# netSpeed.net
KiCad netlist of a schematic drawn in EAGLE
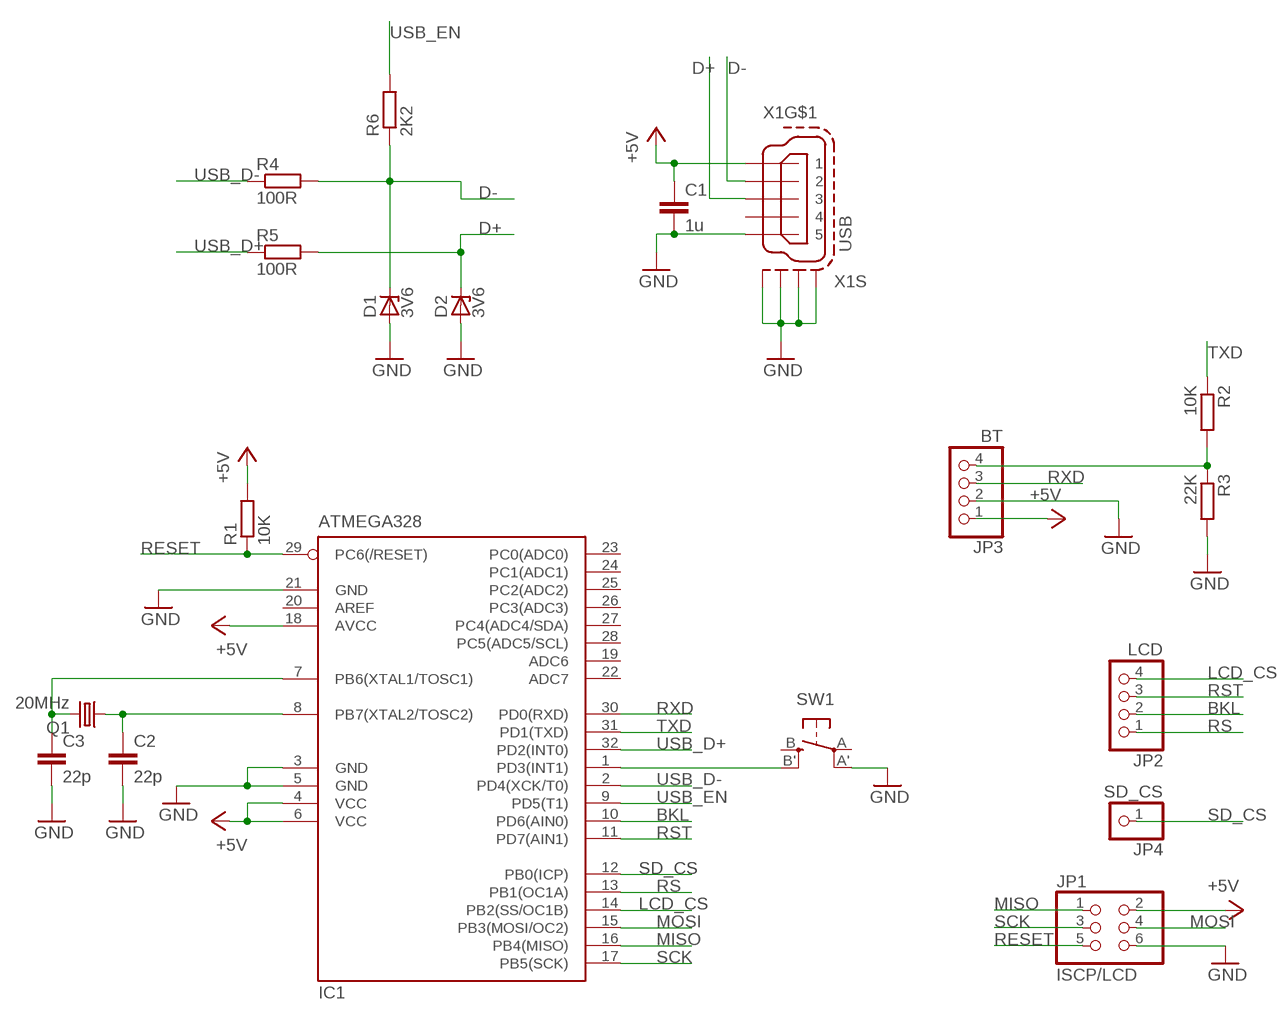
[diagram p0: schematic, sheet 1]

(export (version "E")
  (design (tool "Eeschema 10.0.6"))
  (components
    (comp (ref "C1")
      (value "1u")
      (footprint "eagle-import:C0805")
      (libsource (lib "eagle-import") (part "C-EUC0805"))
    )
    (comp (ref "C2")
      (value "22p")
      (footprint "eagle-import:C0805")
      (libsource (lib "eagle-import") (part "C-EUC0805"))
    )
    (comp (ref "C3")
      (value "22p")
      (footprint "eagle-import:C0805")
      (libsource (lib "eagle-import") (part "C-EUC0805"))
    )
    (comp (ref "D1")
      (value "3V6")
      (footprint "eagle-import:ZDIO-2.5")
      (libsource (lib "eagle-import") (part "ZENER-DIODEZD-2.5"))
    )
    (comp (ref "D2")
      (value "3V6")
      (footprint "eagle-import:ZDIO-2.5")
      (libsource (lib "eagle-import") (part "ZENER-DIODEZD-2.5"))
    )
    (comp (ref "IC1")
      (value "ATMEGA328")
      (footprint "eagle-import:TQFP32-08")
      (fields (field (name "MPN") "ATMEGA8-16AU"))
      (libsource (lib "eagle-import") (part "MEGA8-AI"))
    )
    (comp (ref "JP1")
      (value "ISCP/LCD")
      (footprint "eagle-import:2X03")
      (libsource (lib "eagle-import") (part "PINHD-2X3"))
    )
    (comp (ref "JP2")
      (value "LCD")
      (footprint "eagle-import:1X04")
      (libsource (lib "eagle-import") (part "PINHD-1X4"))
    )
    (comp (ref "JP3")
      (value "BT")
      (footprint "eagle-import:1X04")
      (libsource (lib "eagle-import") (part "PINHD-1X4"))
    )
    (comp (ref "JP4")
      (value "SD_CS")
      (footprint "eagle-import:1X01")
      (libsource (lib "eagle-import") (part "PINHD-1X1"))
    )
    (comp (ref "Q1")
      (value "20MHz")
      (footprint "eagle-import:HC49UP")
      (libsource (lib "eagle-import") (part "CRYSTALHC49UP"))
    )
    (comp (ref "R1")
      (value "10K")
      (footprint "eagle-import:M0805")
      (libsource (lib "eagle-import") (part "R-EU_M0805"))
    )
    (comp (ref "R2")
      (value "10K")
      (footprint "eagle-import:M0805")
      (libsource (lib "eagle-import") (part "R-EU_M0805"))
    )
    (comp (ref "R3")
      (value "22K")
      (footprint "eagle-import:M0805")
      (libsource (lib "eagle-import") (part "R-EU_M0805"))
    )
    (comp (ref "R4")
      (value "100R")
      (footprint "eagle-import:M0805")
      (libsource (lib "eagle-import") (part "R-EU_M0805"))
    )
    (comp (ref "R5")
      (value "100R")
      (footprint "eagle-import:M0805")
      (libsource (lib "eagle-import") (part "R-EU_M0805"))
    )
    (comp (ref "R6")
      (value "2K2")
      (footprint "eagle-import:M0805")
      (libsource (lib "eagle-import") (part "R-EU_M0805"))
    )
    (comp (ref "SW1")
      (value "SPST_TACT-EVQQ2")
      (footprint "eagle-import:EVQ-Q2")
      (libsource (lib "eagle-import") (part "SPST_TACT-EVQQ2"))
    )
    (comp (ref "X1")
      (value "USB")
      (footprint "eagle-import:32005-201")
      (libsource (lib "eagle-import") (part "MINI-USB-SCHIELD-32005-201"))
    )
  )
  (nets
    (net (code "1") (name "+5V") (class "Default")
      (node (ref "C1") (pin "1") (pinfunction "1_1") (pintype "passive"))
      (node (ref "IC1") (pin "18") (pinfunction "AVCC_18") (pintype "power_in"))
      (node (ref "IC1") (pin "4") (pinfunction "VCC_4") (pintype "power_in"))
      (node (ref "IC1") (pin "6") (pinfunction "VCC_6") (pintype "power_in"))
      (node (ref "JP1") (pin "2") (pinfunction "2_2") (pintype "passive"))
      (node (ref "JP3") (pin "1") (pinfunction "1_1") (pintype "passive"))
      (node (ref "R1") (pin "2") (pinfunction "2_2") (pintype "passive"))
      (node (ref "X1") (pin "1") (pinfunction "1_1") (pintype "passive"))
    )
    (net (code "2") (name "/BKL") (class "Default")
      (node (ref "IC1") (pin "10") (pinfunction "PD6(AIN0)_10") (pintype "bidirectional"))
      (node (ref "JP2") (pin "2") (pinfunction "2_2") (pintype "passive"))
    )
    (net (code "3") (name "/D+") (class "Default")
      (node (ref "D2") (pin "C") (pinfunction "C_C") (pintype "passive"))
      (node (ref "R5") (pin "2") (pinfunction "2_2") (pintype "passive"))
      (node (ref "X1") (pin "3") (pinfunction "3_3") (pintype "passive"))
    )
    (net (code "4") (name "/D-") (class "Default")
      (node (ref "D1") (pin "C") (pinfunction "C_C") (pintype "passive"))
      (node (ref "R4") (pin "2") (pinfunction "2_2") (pintype "passive"))
      (node (ref "R6") (pin "1") (pinfunction "1_1") (pintype "passive"))
      (node (ref "X1") (pin "2") (pinfunction "2_2") (pintype "passive"))
    )
    (net (code "5") (name "/LCD_CS") (class "Default")
      (node (ref "IC1") (pin "14") (pinfunction "PB2(SS/OC1B)_14") (pintype "bidirectional"))
      (node (ref "JP2") (pin "4") (pinfunction "4_4") (pintype "passive"))
    )
    (net (code "6") (name "/MISO") (class "Default")
      (node (ref "IC1") (pin "16") (pinfunction "PB4(MISO)_16") (pintype "bidirectional"))
      (node (ref "JP1") (pin "1") (pinfunction "1_1") (pintype "passive"))
    )
    (net (code "7") (name "/MOSI") (class "Default")
      (node (ref "IC1") (pin "15") (pinfunction "PB3(MOSI/OC2)_15") (pintype "bidirectional"))
      (node (ref "JP1") (pin "4") (pinfunction "4_4") (pintype "passive"))
    )
    (net (code "8") (name "/RESET") (class "Default")
      (node (ref "IC1") (pin "29") (pinfunction "PC6(/RESET)_29") (pintype "bidirectional"))
      (node (ref "JP1") (pin "5") (pinfunction "5_5") (pintype "passive"))
      (node (ref "R1") (pin "1") (pinfunction "1_1") (pintype "passive"))
    )
    (net (code "9") (name "/RS") (class "Default")
      (node (ref "IC1") (pin "13") (pinfunction "PB1(OC1A)_13") (pintype "bidirectional"))
      (node (ref "JP2") (pin "1") (pinfunction "1_1") (pintype "passive"))
    )
    (net (code "10") (name "/RST") (class "Default")
      (node (ref "IC1") (pin "11") (pinfunction "PD7(AIN1)_11") (pintype "bidirectional"))
      (node (ref "JP2") (pin "3") (pinfunction "3_3") (pintype "passive"))
    )
    (net (code "11") (name "/RXD") (class "Default")
      (node (ref "IC1") (pin "30") (pinfunction "PD0(RXD)_30") (pintype "bidirectional"))
      (node (ref "JP3") (pin "3") (pinfunction "3_3") (pintype "passive"))
    )
    (net (code "12") (name "/SCK") (class "Default")
      (node (ref "IC1") (pin "17") (pinfunction "PB5(SCK)_17") (pintype "bidirectional"))
      (node (ref "JP1") (pin "3") (pinfunction "3_3") (pintype "passive"))
    )
    (net (code "13") (name "/SD_CS") (class "Default")
      (node (ref "IC1") (pin "12") (pinfunction "PB0(ICP)_12") (pintype "bidirectional"))
      (node (ref "JP4") (pin "1") (pinfunction "1_1") (pintype "passive"))
    )
    (net (code "14") (name "/TXD") (class "Default")
      (node (ref "IC1") (pin "31") (pinfunction "PD1(TXD)_31") (pintype "bidirectional"))
      (node (ref "R2") (pin "1") (pinfunction "1_1") (pintype "passive"))
    )
    (net (code "15") (name "/USB_D+") (class "Default")
      (node (ref "IC1") (pin "32") (pinfunction "PD2(INT0)_32") (pintype "bidirectional"))
      (node (ref "R5") (pin "1") (pinfunction "1_1") (pintype "passive"))
    )
    (net (code "16") (name "/USB_D-") (class "Default")
      (node (ref "IC1") (pin "2") (pinfunction "PD4(XCK/T0)_2") (pintype "bidirectional"))
      (node (ref "R4") (pin "1") (pinfunction "1_1") (pintype "passive"))
    )
    (net (code "17") (name "/USB_EN") (class "Default")
      (node (ref "IC1") (pin "9") (pinfunction "PD5(T1)_9") (pintype "bidirectional"))
      (node (ref "R6") (pin "2") (pinfunction "2_2") (pintype "passive"))
    )
    (net (code "18") (name "GND") (class "Default")
      (node (ref "C1") (pin "2") (pinfunction "2_2") (pintype "passive"))
      (node (ref "C2") (pin "2") (pinfunction "2_2") (pintype "passive"))
      (node (ref "C3") (pin "2") (pinfunction "2_2") (pintype "passive"))
      (node (ref "D1") (pin "A") (pinfunction "A_A") (pintype "passive"))
      (node (ref "D2") (pin "A") (pinfunction "A_A") (pintype "passive"))
      (node (ref "IC1") (pin "21") (pinfunction "GND_21") (pintype "power_in"))
      (node (ref "IC1") (pin "3") (pinfunction "GND_3") (pintype "power_in"))
      (node (ref "IC1") (pin "5") (pinfunction "GND_5") (pintype "power_in"))
      (node (ref "JP1") (pin "6") (pinfunction "6_6") (pintype "passive"))
      (node (ref "JP3") (pin "2") (pinfunction "2_2") (pintype "passive"))
      (node (ref "R3") (pin "2") (pinfunction "2_2") (pintype "passive"))
      (node (ref "SW1") (pin "A'") (pinfunction "P1_A'") (pintype "passive"))
      (node (ref "X1") (pin "5") (pinfunction "5_5") (pintype "passive"))
      (node (ref "X1") (pin "M1") (pinfunction "S1_M1") (pintype "passive"))
      (node (ref "X1") (pin "M2") (pinfunction "S2_M2") (pintype "passive"))
      (node (ref "X1") (pin "M3") (pinfunction "S3_M3") (pintype "passive"))
      (node (ref "X1") (pin "M4") (pinfunction "S4_M4") (pintype "passive"))
    )
    (net (code "19") (name "Net-(IC1-PB6(XTAL1{slash}TOSC1))") (class "Default")
      (node (ref "C3") (pin "1") (pinfunction "1_1") (pintype "passive"))
      (node (ref "IC1") (pin "7") (pinfunction "PB6(XTAL1/TOSC1)_7") (pintype "bidirectional"))
      (node (ref "Q1") (pin "2") (pinfunction "2_2") (pintype "passive"))
    )
    (net (code "20") (name "Net-(IC1-PB7(XTAL2{slash}TOSC2))") (class "Default")
      (node (ref "C2") (pin "1") (pinfunction "1_1") (pintype "passive"))
      (node (ref "IC1") (pin "8") (pinfunction "PB7(XTAL2/TOSC2)_8") (pintype "bidirectional"))
      (node (ref "Q1") (pin "1") (pinfunction "1_1") (pintype "passive"))
    )
    (net (code "21") (name "Net-(IC1-PD3(INT1))") (class "Default")
      (node (ref "IC1") (pin "1") (pinfunction "PD3(INT1)_1") (pintype "bidirectional"))
      (node (ref "SW1") (pin "B'") (pinfunction "S1_B'") (pintype "passive"))
    )
    (net (code "22") (name "Net-(JP3-Pad4)") (class "Default")
      (node (ref "JP3") (pin "4") (pinfunction "4_4") (pintype "passive"))
      (node (ref "R2") (pin "2") (pinfunction "2_2") (pintype "passive"))
      (node (ref "R3") (pin "1") (pinfunction "1_1") (pintype "passive"))
    )
    (net (code "23") (name "unconnected-(IC1-ADC6-Pad19)") (class "Default")
      (node (ref "IC1") (pin "19") (pinfunction "ADC6_19") (pintype "bidirectional"))
    )
    (net (code "24") (name "unconnected-(IC1-ADC7-Pad22)") (class "Default")
      (node (ref "IC1") (pin "22") (pinfunction "ADC7_22") (pintype "bidirectional"))
    )
    (net (code "25") (name "unconnected-(IC1-AREF-Pad20)") (class "Default")
      (node (ref "IC1") (pin "20") (pinfunction "AREF_20") (pintype "passive"))
    )
    (net (code "26") (name "unconnected-(IC1-PC0(ADC0)-Pad23)") (class "Default")
      (node (ref "IC1") (pin "23") (pinfunction "PC0(ADC0)_23") (pintype "bidirectional"))
    )
    (net (code "27") (name "unconnected-(IC1-PC1(ADC1)-Pad24)") (class "Default")
      (node (ref "IC1") (pin "24") (pinfunction "PC1(ADC1)_24") (pintype "bidirectional"))
    )
    (net (code "28") (name "unconnected-(IC1-PC2(ADC2)-Pad25)") (class "Default")
      (node (ref "IC1") (pin "25") (pinfunction "PC2(ADC2)_25") (pintype "bidirectional"))
    )
    (net (code "29") (name "unconnected-(IC1-PC3(ADC3)-Pad26)") (class "Default")
      (node (ref "IC1") (pin "26") (pinfunction "PC3(ADC3)_26") (pintype "bidirectional"))
    )
    (net (code "30") (name "unconnected-(IC1-PC4(ADC4{slash}SDA)-Pad27)") (class "Default")
      (node (ref "IC1") (pin "27") (pinfunction "PC4(ADC4/SDA)_27") (pintype "bidirectional"))
    )
    (net (code "31") (name "unconnected-(IC1-PC5(ADC5{slash}SCL)-Pad28)") (class "Default")
      (node (ref "IC1") (pin "28") (pinfunction "PC5(ADC5/SCL)_28") (pintype "bidirectional"))
    )
    (net (code "32") (name "unconnected-(SW1-P-PadA)") (class "Default")
      (node (ref "SW1") (pin "A") (pinfunction "P_A") (pintype "passive"))
    )
    (net (code "33") (name "unconnected-(SW1-S-PadB)") (class "Default")
      (node (ref "SW1") (pin "B") (pinfunction "S_B") (pintype "passive"))
    )
    (net (code "34") (name "unconnected-(X1-Pad4)") (class "Default")
      (node (ref "X1") (pin "4") (pinfunction "4_4") (pintype "passive"))
    )
  )
)
